# RECOVERY_USBC.net
KiCad netlist of a schematic drawn in Altium Designer
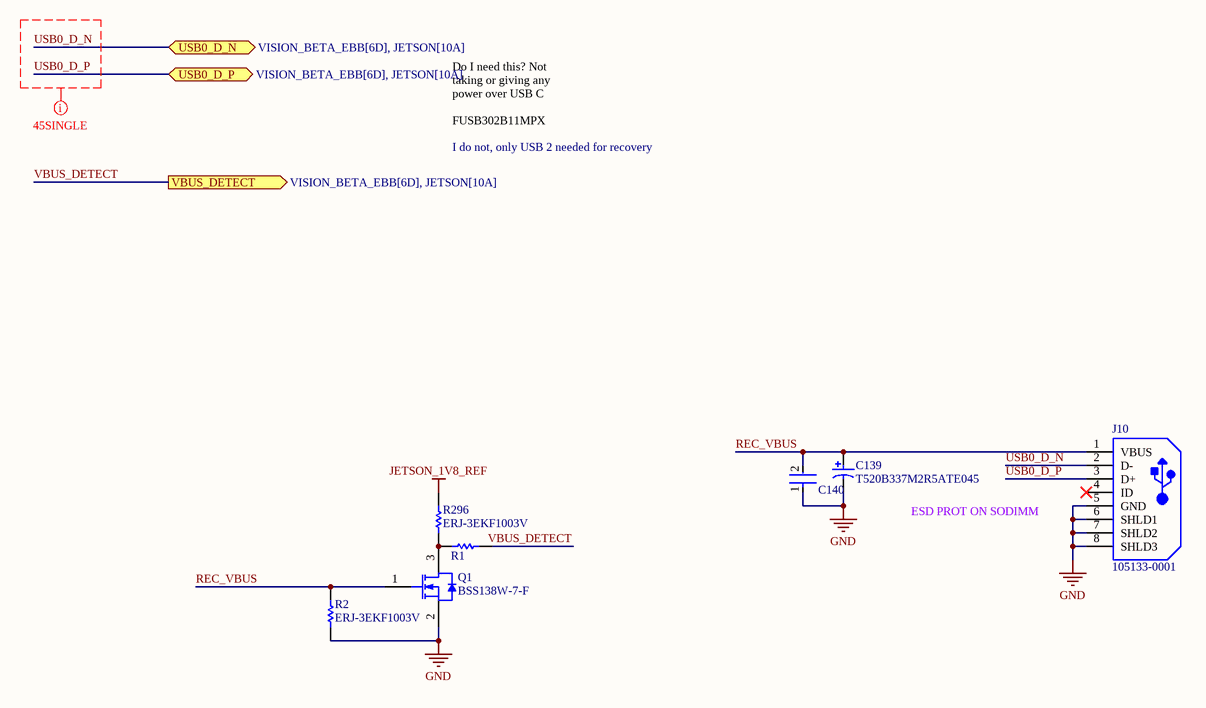
[diagram p0: RECOVERY_USBC.SchDoc]

(export (version "E")
  (design (tool "Eeschema 10.0.6"))
  (components
    (comp (ref "C139")
      (value "T520B337M2R5ATE045")
      (footprint "KEMT-520-B-2_M")
      (description "Tantalum Capacitor, 330 uF, +/- 20%, 2.5 V, -55 to 105 degC, 2-Pin Molded, RoHS, Tape and Reel")
      (libsource (lib "Altium Content Vault") (part "CAP-P-2"))
    )
    (comp (ref "C140")
      (value "C1005X7R1H104K050BB")
      (footprint "FP-C1005-050-0_05-IPC_C")
      (description "Multilayer Ceramic Capacitors 100nF ±10% 50V X7R SMD 0402")
      (fields (field (name "VOLTAGE") "50V") (field (name "TOLERANCE") "10%"))
      (libsource (lib "Altium Content Vault") (part "b4654b650e69147ec39a6b967a45e02"))
    )
    (comp (ref "J10")
      (value "105133-0001")
      (footprint "MOLX-105133-0001_V")
      (description "Micro-USB B Receptacle, Vertical, -30 to 85 degC, 5-Pin SMD, RoHS, Tape and Reel")
      (fields (field (name "MANUFACTURER") "Molex"))
      (libsource (lib "Altium Content Vault") (part "USB-5-3SHLD"))
    )
    (comp (ref "Q1")
      (value "BSS138W-7-F")
      (footprint "DIOD-SOT323-3_V")
      (fields (field (name "MANUFACTURER") "DiodesIncorporated"))
      (libsource (lib "Altium Content Vault") (part "NEMOS-GSD-3"))
    )
    (comp (ref "R1")
      (value "0402 JUMPER")
      (footprint "RESC1005X40X25ML05T05")
      (description "READ THE NAME")
      (libsource (lib "Space Concordia") (part "CMP-009-00206-2"))
    )
    (comp (ref "R2")
      (value "ERJ-3EKF1003V")
      (footprint "RESC1608X55X30ML15T15")
      (fields (field (name "MANUFACTURER") "Panasonic"))
      (libsource (lib "Altium Content Vault") (part "RES"))
    )
    (comp (ref "R296")
      (value "ERJ-3EKF1003V")
      (footprint "RESC1608X55X30ML15T15")
      (fields (field (name "MANUFACTURER") "Panasonic"))
      (libsource (lib "Altium Content Vault") (part "RES"))
    )
  )
  (nets
    (net (code "1") (name "/REC_VBUS") (class "Default")
      (node (ref "C139") (pin "1") (pinfunction "1_1") (pintype "passive"))
      (node (ref "C140") (pin "2") (pinfunction "2_2") (pintype "passive"))
      (node (ref "J10") (pin "1") (pinfunction "VBUS_1") (pintype "passive"))
      (node (ref "Q1") (pin "1") (pinfunction "G_1") (pintype "passive"))
      (node (ref "R2") (pin "2") (pinfunction "2_2") (pintype "passive"))
    )
    (net (code "2") (name "/USB0_D_N") (class "Default")
      (node (ref "J10") (pin "2") (pinfunction "D-_2") (pintype "passive"))
    )
    (net (code "3") (name "/USB0_D_P") (class "Default")
      (node (ref "J10") (pin "3") (pinfunction "D+_3") (pintype "passive"))
    )
    (net (code "4") (name "/VBUS_DETECT") (class "Default")
      (node (ref "R1") (pin "2") (pinfunction "2_2") (pintype "passive"))
    )
    (net (code "5") (name "GND") (class "Default")
      (node (ref "C139") (pin "2") (pinfunction "2_2") (pintype "passive"))
      (node (ref "C140") (pin "1") (pinfunction "1_1") (pintype "passive"))
      (node (ref "J10") (pin "5") (pinfunction "GND_5") (pintype "passive"))
      (node (ref "J10") (pin "6") (pinfunction "SHLD1_6") (pintype "passive"))
      (node (ref "J10") (pin "7") (pinfunction "SHLD2_7") (pintype "passive"))
      (node (ref "J10") (pin "8") (pinfunction "SHLD3_8") (pintype "passive"))
      (node (ref "Q1") (pin "2") (pinfunction "S_2") (pintype "passive"))
      (node (ref "R2") (pin "1") (pinfunction "1_1") (pintype "passive"))
    )
    (net (code "6") (name "JETSON_1V8_REF") (class "Default")
      (node (ref "R296") (pin "2") (pinfunction "2_2") (pintype "passive"))
    )
    (net (code "7") (name "Net-(Q1-D)") (class "Default")
      (node (ref "Q1") (pin "3") (pinfunction "D_3") (pintype "passive"))
      (node (ref "R1") (pin "1") (pinfunction "1_1") (pintype "passive"))
      (node (ref "R296") (pin "1") (pinfunction "1_1") (pintype "passive"))
    )
    (net (code "8") (name "unconnected-(J10-ID-Pad4)") (class "Default")
      (node (ref "J10") (pin "4") (pinfunction "ID_4") (pintype "passive+no_connect"))
    )
  )
)
